# Sheet1.net
KiCad netlist of a schematic drawn in Altium Designer
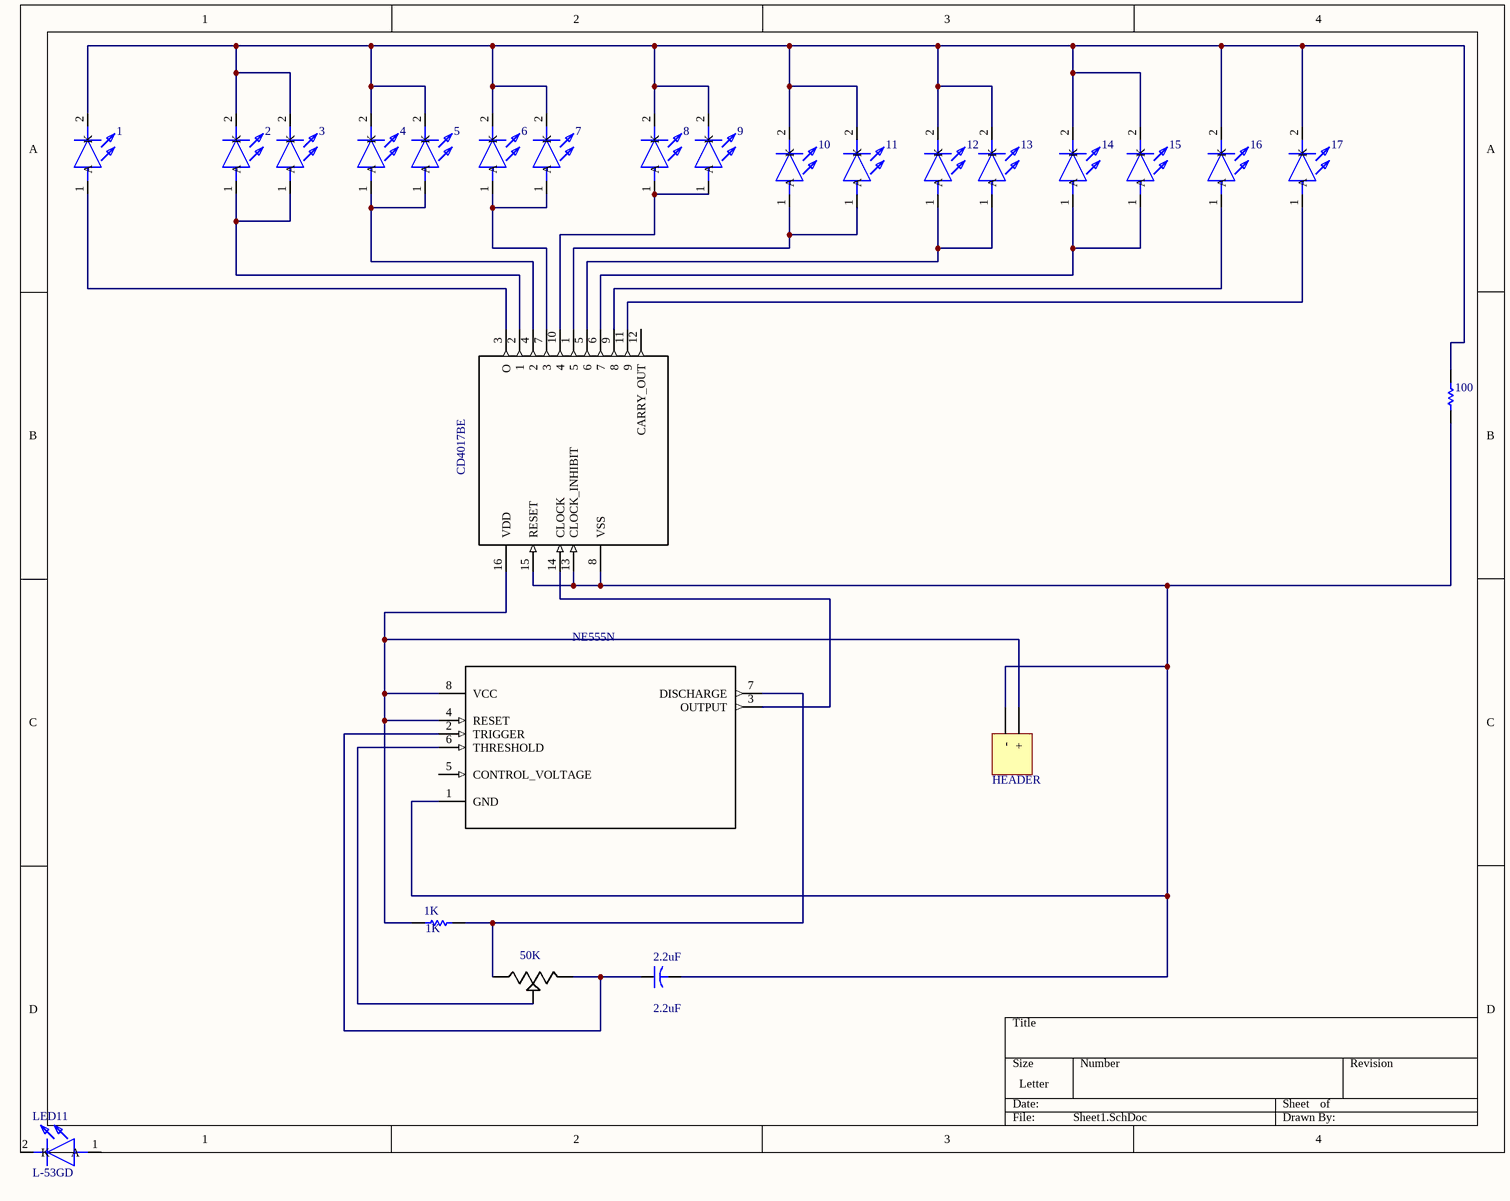
[diagram p0: Sheet1.SchDoc]

(export (version "E")
  (design (tool "Eeschema 10.0.6"))
  (components
    (comp (ref "1")
      (value "1")
      (footprint "SamacSys:L-53GD")
      (description "LED")
      (fields (field (name "MANUFACTURER_PART_NUMBER") "L-53GD") (field (name "RS PART NUMBER") "2286004A"))
      (libsource (lib "SamacSys") (part "L-53GD"))
    )
    (comp (ref "1K")
      (value "1K")
      (footprint "AXIAL-0.3")
      (description "Resistor")
      (fields (field (name "Comment") "Res1") (field (name "PUBLISHER") "Altium Limited"))
      (libsource (lib "Miscellaneous Devices") (part "Res1"))
    )
    (comp (ref "2")
      (value "1")
      (footprint "SamacSys:L-53GD")
      (description "LED")
      (fields (field (name "MANUFACTURER_PART_NUMBER") "L-53GD") (field (name "RS PART NUMBER") "2286004A"))
      (libsource (lib "SamacSys") (part "L-53GD"))
    )
    (comp (ref "2.2uF")
      (value "2.2uF")
      (footprint "CAPR5-4X5")
      (description "Capacitor")
      (fields (field (name "Comment") "Cap2") (field (name "PUBLISHER") "Altium Limited"))
      (libsource (lib "Miscellaneous Devices") (part "Cap2"))
    )
    (comp (ref "3")
      (value "1")
      (footprint "SamacSys:L-53GD")
      (description "LED")
      (fields (field (name "MANUFACTURER_PART_NUMBER") "L-53GD") (field (name "RS PART NUMBER") "2286004A"))
      (libsource (lib "SamacSys") (part "L-53GD"))
    )
    (comp (ref "4")
      (value "3")
      (footprint "SamacSys:L-53GD")
      (description "LED")
      (fields (field (name "MANUFACTURER_PART_NUMBER") "L-53GD") (field (name "RS PART NUMBER") "2286004A"))
      (libsource (lib "SamacSys") (part "L-53GD"))
    )
    (comp (ref "5")
      (value "1")
      (footprint "SamacSys:L-53GD")
      (description "LED")
      (fields (field (name "MANUFACTURER_PART_NUMBER") "L-53GD") (field (name "RS PART NUMBER") "2286004A"))
      (libsource (lib "SamacSys") (part "L-53GD"))
    )
    (comp (ref "6")
      (value "4")
      (footprint "SamacSys:L-53GD")
      (description "LED")
      (fields (field (name "MANUFACTURER_PART_NUMBER") "L-53GD") (field (name "RS PART NUMBER") "2286004A"))
      (libsource (lib "SamacSys") (part "L-53GD"))
    )
    (comp (ref "7")
      (value "1")
      (footprint "SamacSys:L-53GD")
      (description "LED")
      (fields (field (name "MANUFACTURER_PART_NUMBER") "L-53GD") (field (name "RS PART NUMBER") "2286004A"))
      (libsource (lib "SamacSys") (part "L-53GD"))
    )
    (comp (ref "8")
      (value "5")
      (footprint "SamacSys:L-53GD")
      (description "LED")
      (fields (field (name "MANUFACTURER_PART_NUMBER") "L-53GD") (field (name "RS PART NUMBER") "2286004A"))
      (libsource (lib "SamacSys") (part "L-53GD"))
    )
    (comp (ref "9")
      (value "1")
      (footprint "SamacSys:L-53GD")
      (description "LED")
      (fields (field (name "MANUFACTURER_PART_NUMBER") "L-53GD") (field (name "RS PART NUMBER") "2286004A"))
      (libsource (lib "SamacSys") (part "L-53GD"))
    )
    (comp (ref "10")
      (value "6")
      (footprint "SamacSys:L-53GD")
      (description "LED")
      (fields (field (name "MANUFACTURER_PART_NUMBER") "L-53GD") (field (name "RS PART NUMBER") "2286004A"))
      (libsource (lib "SamacSys") (part "L-53GD"))
    )
    (comp (ref "11")
      (value "1")
      (footprint "SamacSys:L-53GD")
      (description "LED")
      (fields (field (name "MANUFACTURER_PART_NUMBER") "L-53GD") (field (name "RS PART NUMBER") "2286004A"))
      (libsource (lib "SamacSys") (part "L-53GD"))
    )
    (comp (ref "12")
      (value "7")
      (footprint "SamacSys:L-53GD")
      (description "LED")
      (fields (field (name "MANUFACTURER_PART_NUMBER") "L-53GD") (field (name "RS PART NUMBER") "2286004A"))
      (libsource (lib "SamacSys") (part "L-53GD"))
    )
    (comp (ref "13")
      (value "1")
      (footprint "SamacSys:L-53GD")
      (description "LED")
      (fields (field (name "MANUFACTURER_PART_NUMBER") "L-53GD") (field (name "RS PART NUMBER") "2286004A"))
      (libsource (lib "SamacSys") (part "L-53GD"))
    )
    (comp (ref "14")
      (value "8")
      (footprint "SamacSys:L-53GD")
      (description "LED")
      (fields (field (name "MANUFACTURER_PART_NUMBER") "L-53GD") (field (name "RS PART NUMBER") "2286004A"))
      (libsource (lib "SamacSys") (part "L-53GD"))
    )
    (comp (ref "15")
      (value "1")
      (footprint "SamacSys:L-53GD")
      (description "LED")
      (fields (field (name "MANUFACTURER_PART_NUMBER") "L-53GD") (field (name "RS PART NUMBER") "2286004A"))
      (libsource (lib "SamacSys") (part "L-53GD"))
    )
    (comp (ref "16")
      (value "9")
      (footprint "SamacSys:L-53GD")
      (description "LED")
      (fields (field (name "MANUFACTURER_PART_NUMBER") "L-53GD") (field (name "RS PART NUMBER") "2286004A"))
      (libsource (lib "SamacSys") (part "L-53GD"))
    )
    (comp (ref "17")
      (value "10")
      (footprint "SamacSys:L-53GD")
      (description "LED")
      (fields (field (name "MANUFACTURER_PART_NUMBER") "L-53GD") (field (name "RS PART NUMBER") "2286004A"))
      (libsource (lib "SamacSys") (part "L-53GD"))
    )
    (comp (ref "50K")
      (value "100K")
      (footprint "*TRIM_EVN-D8AA03B14")
      (description "Trimmer; Carbon; Rest 10 Kilohms; PCB; 1 Turn; Pwr-Rtg 0.1 W; Linear; Top Adj; 6 mm SQ")
      (fields (field (name "MF") "Panasonic Electronic") (field (name "MP") "EVN-D8AA03B14"))
      (libsource (lib "EVN-D8AA03B14") (part "EVN-D8AA03B14"))
    )
    (comp (ref "100")
      (value "120")
      (footprint "AXIAL-0.3")
      (description "Resistor")
      (fields (field (name "PUBLISHER") "Altium Limited"))
      (libsource (lib "Miscellaneous Devices") (part "Res1"))
    )
    (comp (ref "CD4017BE")
      (value "CD4017BE")
      (footprint "*DIP254P762X508-16")
      (description "IC Mos 4017/CD4017BE HARRIS")
      (fields (field (name "MF") "Texas"))
      (libsource (lib "CD4017BE") (part "CD4017BE"))
    )
    (comp (ref "HEADER")
      (value "Header 2")
      (footprint "HDR1X2")
      (description "Header, 2-Pin")
      (fields (field (name "PUBLISHER") "Altium Limited"))
      (libsource (lib "Miscellaneous Connectors") (part "Header 2"))
    )
    (comp (ref "LED11")
      (value "L-53GD")
      (footprint "SamacSys:L-53GD")
      (description "LED")
      (fields (field (name "RS PART NUMBER") "2286004A"))
      (libsource (lib "*") (part "L-53GD"))
    )
    (comp (ref "NE555N")
      (value "NE555N")
      (footprint "*DIP254P762X533-8")
      (fields (field (name "MF") "ON Semiconductor"))
      (libsource (lib "NE555N") (part "NE555N"))
    )
  )
  (nets
    (net (code "1") (name "Net-(1-A)") (class "Default")
      (node (ref "1") (pin "1") (pinfunction "A_1") (pintype "passive"))
      (node (ref "CD4017BE") (pin "3") (pinfunction "O_3") (pintype "output"))
    )
    (net (code "2") (name "Net-(1-K)") (class "Default")
      (node (ref "1") (pin "2") (pinfunction "K_2") (pintype "passive"))
      (node (ref "10") (pin "2") (pinfunction "K_2") (pintype "passive"))
      (node (ref "100") (pin "1") (pinfunction "1_1") (pintype "passive"))
      (node (ref "11") (pin "2") (pinfunction "K_2") (pintype "passive"))
      (node (ref "12") (pin "2") (pinfunction "K_2") (pintype "passive"))
      (node (ref "13") (pin "2") (pinfunction "K_2") (pintype "passive"))
      (node (ref "14") (pin "2") (pinfunction "K_2") (pintype "passive"))
      (node (ref "15") (pin "2") (pinfunction "K_2") (pintype "passive"))
      (node (ref "16") (pin "2") (pinfunction "K_2") (pintype "passive"))
      (node (ref "17") (pin "2") (pinfunction "K_2") (pintype "passive"))
      (node (ref "2") (pin "2") (pinfunction "K_2") (pintype "passive"))
      (node (ref "3") (pin "2") (pinfunction "K_2") (pintype "passive"))
      (node (ref "4") (pin "2") (pinfunction "K_2") (pintype "passive"))
      (node (ref "5") (pin "2") (pinfunction "K_2") (pintype "passive"))
      (node (ref "6") (pin "2") (pinfunction "K_2") (pintype "passive"))
      (node (ref "7") (pin "2") (pinfunction "K_2") (pintype "passive"))
      (node (ref "8") (pin "2") (pinfunction "K_2") (pintype "passive"))
      (node (ref "9") (pin "2") (pinfunction "K_2") (pintype "passive"))
    )
    (net (code "3") (name "Net-(2-A)") (class "Default")
      (node (ref "2") (pin "1") (pinfunction "A_1") (pintype "passive"))
      (node (ref "3") (pin "1") (pinfunction "A_1") (pintype "passive"))
      (node (ref "CD4017BE") (pin "2") (pinfunction "1_2") (pintype "output"))
    )
    (net (code "4") (name "Net-(4-A)") (class "Default")
      (node (ref "4") (pin "1") (pinfunction "A_1") (pintype "passive"))
      (node (ref "5") (pin "1") (pinfunction "A_1") (pintype "passive"))
      (node (ref "CD4017BE") (pin "4") (pinfunction "2_4") (pintype "output"))
    )
    (net (code "5") (name "Net-(6-A)") (class "Default")
      (node (ref "6") (pin "1") (pinfunction "A_1") (pintype "passive"))
      (node (ref "7") (pin "1") (pinfunction "A_1") (pintype "passive"))
      (node (ref "CD4017BE") (pin "7") (pinfunction "3_7") (pintype "output"))
    )
    (net (code "6") (name "Net-(8-A)") (class "Default")
      (node (ref "8") (pin "1") (pinfunction "A_1") (pintype "passive"))
      (node (ref "9") (pin "1") (pinfunction "A_1") (pintype "passive"))
      (node (ref "CD4017BE") (pin "10") (pinfunction "4_10") (pintype "output"))
    )
    (net (code "7") (name "Net-(10-A)") (class "Default")
      (node (ref "10") (pin "1") (pinfunction "A_1") (pintype "passive"))
      (node (ref "11") (pin "1") (pinfunction "A_1") (pintype "passive"))
      (node (ref "CD4017BE") (pin "1") (pinfunction "5_1") (pintype "output"))
    )
    (net (code "8") (name "Net-(12-A)") (class "Default")
      (node (ref "12") (pin "1") (pinfunction "A_1") (pintype "passive"))
      (node (ref "13") (pin "1") (pinfunction "A_1") (pintype "passive"))
      (node (ref "CD4017BE") (pin "5") (pinfunction "6_5") (pintype "output"))
    )
    (net (code "9") (name "Net-(14-A)") (class "Default")
      (node (ref "14") (pin "1") (pinfunction "A_1") (pintype "passive"))
      (node (ref "15") (pin "1") (pinfunction "A_1") (pintype "passive"))
      (node (ref "CD4017BE") (pin "6") (pinfunction "7_6") (pintype "output"))
    )
    (net (code "10") (name "Net-(16-A)") (class "Default")
      (node (ref "16") (pin "1") (pinfunction "A_1") (pintype "passive"))
      (node (ref "CD4017BE") (pin "9") (pinfunction "8_9") (pintype "output"))
    )
    (net (code "11") (name "Net-(17-A)") (class "Default")
      (node (ref "17") (pin "1") (pinfunction "A_1") (pintype "passive"))
      (node (ref "CD4017BE") (pin "11") (pinfunction "9_11") (pintype "output"))
    )
    (net (code "12") (name "Net-(CD4017BE-CLOCK)") (class "Default")
      (node (ref "CD4017BE") (pin "14") (pinfunction "CLOCK_14") (pintype "input"))
      (node (ref "NE555N") (pin "3") (pinfunction "OUTPUT_3") (pintype "output"))
    )
    (net (code "13") (name "Net-(CD4017BE-CLOCK_INHIBIT)") (class "Default")
      (node (ref "100") (pin "2") (pinfunction "2_2") (pintype "passive"))
      (node (ref "2.2uF") (pin "2") (pinfunction "2_2") (pintype "passive"))
      (node (ref "CD4017BE") (pin "13") (pinfunction "CLOCK_INHIBIT_13") (pintype "input"))
      (node (ref "CD4017BE") (pin "15") (pinfunction "RESET_15") (pintype "input"))
      (node (ref "CD4017BE") (pin "8") (pinfunction "VSS_8") (pintype "power_in"))
      (node (ref "HEADER") (pin "2") (pinfunction "-_2") (pintype "passive"))
      (node (ref "NE555N") (pin "1") (pinfunction "GND_1") (pintype "passive"))
    )
    (net (code "14") (name "Net-(CD4017BE-VDD)") (class "Default")
      (node (ref "1K") (pin "1") (pinfunction "1_1") (pintype "passive"))
      (node (ref "CD4017BE") (pin "16") (pinfunction "VDD_16") (pintype "power_in"))
      (node (ref "HEADER") (pin "1") (pinfunction "+_1") (pintype "passive"))
      (node (ref "NE555N") (pin "4") (pinfunction "RESET_4") (pintype "input"))
      (node (ref "NE555N") (pin "8") (pinfunction "VCC_8") (pintype "power_in"))
    )
    (net (code "15") (name "Net-(NE555N-DISCHARGE)") (class "Default")
      (node (ref "1K") (pin "2") (pinfunction "2_2") (pintype "passive"))
      (node (ref "50K") (pin "1") (pinfunction "1_1") (pintype "passive"))
      (node (ref "NE555N") (pin "7") (pinfunction "DISCHARGE_7") (pintype "output"))
    )
    (net (code "16") (name "Net-(NE555N-THRESHOLD)") (class "Default")
      (node (ref "50K") (pin "2") (pinfunction "2_2") (pintype "passive"))
      (node (ref "NE555N") (pin "6") (pinfunction "THRESHOLD_6") (pintype "input"))
    )
    (net (code "17") (name "Net-(NE555N-TRIGGER)") (class "Default")
      (node (ref "2.2uF") (pin "1") (pinfunction "1_1") (pintype "passive"))
      (node (ref "50K") (pin "3") (pinfunction "3_3") (pintype "passive"))
      (node (ref "NE555N") (pin "2") (pinfunction "TRIGGER_2") (pintype "input"))
    )
    (net (code "18") (name "unconnected-(CD4017BE-CARRY_OUT-Pad12)") (class "Default")
      (node (ref "CD4017BE") (pin "12") (pinfunction "CARRY_OUT_12") (pintype "output"))
    )
    (net (code "19") (name "unconnected-(LED11-A-Pad1)") (class "Default")
      (node (ref "LED11") (pin "1") (pinfunction "A_1") (pintype "passive"))
    )
    (net (code "20") (name "unconnected-(LED11-K-Pad2)") (class "Default")
      (node (ref "LED11") (pin "2") (pinfunction "K_2") (pintype "passive"))
    )
    (net (code "21") (name "unconnected-(NE555N-CONTROL_VOLTAGE-Pad5)") (class "Default")
      (node (ref "NE555N") (pin "5") (pinfunction "CONTROL_VOLTAGE_5") (pintype "input"))
    )
  )
)
